# MAGI_sBatteryPowerMega-Python.net
KiCad netlist of a schematic drawn in Altium Designer
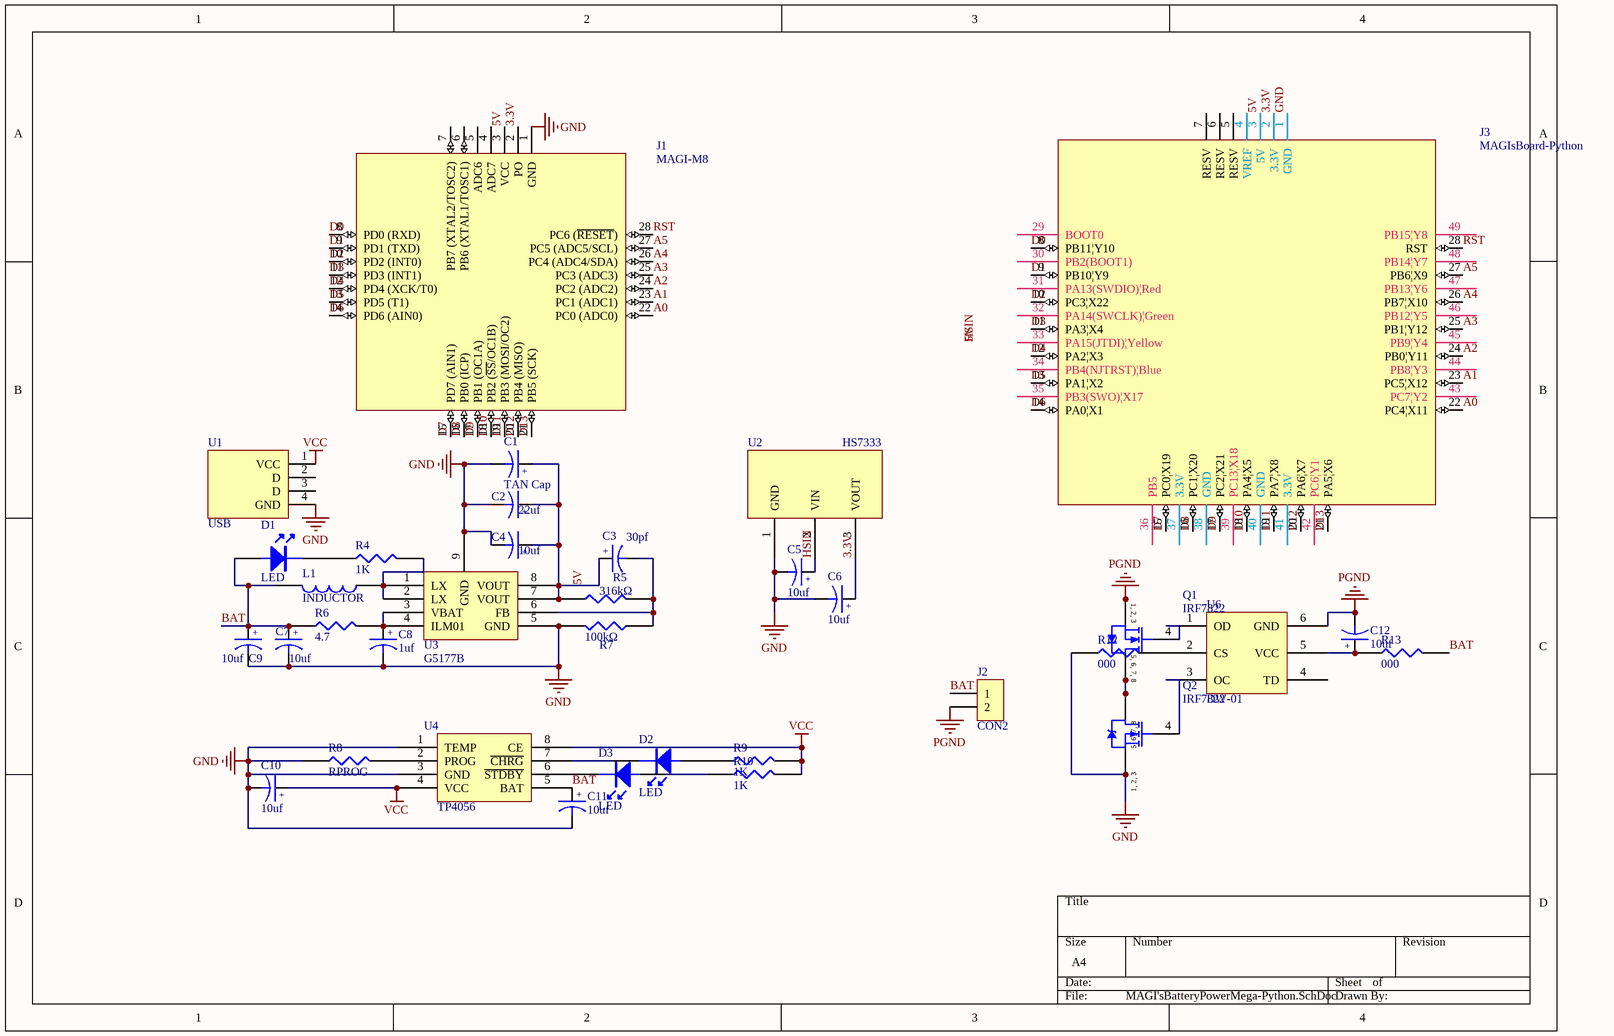
[diagram p0: MAGI'sBatteryPowerMega-Python.SchDoc]

(export (version "E")
  (design (tool "Eeschema 10.0.6"))
  (components
    (comp (ref "C1")
      (value "TAN Cap")
      (footprint "TAN-D-7343")
      (description "Capacitor")
      (libsource (lib "电容器") (part "CAPACITOR POL"))
    )
    (comp (ref "C2")
      (value "22uf")
      (footprint "14-1210")
      (description "Capacitor")
      (libsource (lib "电容器") (part "CAPACITOR POL"))
    )
    (comp (ref "C3")
      (value "30pf")
      (footprint "6-0805_N")
      (description "Capacitor")
      (libsource (lib "电容器") (part "CAPACITOR POL"))
    )
    (comp (ref "C4")
      (value "10uf")
      (footprint "6-0805_N")
      (description "Capacitor")
      (libsource (lib "电容器") (part "CAPACITOR POL"))
    )
    (comp (ref "C5")
      (value "10uf")
      (footprint "6-0805_N")
      (description "Capacitor")
      (libsource (lib "电容器") (part "CAPACITOR POL"))
    )
    (comp (ref "C6")
      (value "10uf")
      (footprint "6-0805_N")
      (description "Capacitor")
      (libsource (lib "电容器") (part "CAPACITOR POL"))
    )
    (comp (ref "C7")
      (value "10uf")
      (footprint "6-0805_N")
      (description "Capacitor")
      (libsource (lib "电容器") (part "CAPACITOR POL"))
    )
    (comp (ref "C8")
      (value "1uf")
      (footprint "6-0805_N")
      (description "Capacitor")
      (libsource (lib "电容器") (part "CAPACITOR POL"))
    )
    (comp (ref "C9")
      (value "10uf")
      (footprint "6-0805_N")
      (description "Capacitor")
      (libsource (lib "电容器") (part "CAPACITOR POL"))
    )
    (comp (ref "C10")
      (value "10uf")
      (footprint "6-0805_N")
      (description "Capacitor")
      (libsource (lib "电容器") (part "CAPACITOR POL"))
    )
    (comp (ref "C11")
      (value "10uf")
      (footprint "6-0805_N")
      (description "Capacitor")
      (libsource (lib "电容器") (part "CAPACITOR POL"))
    )
    (comp (ref "C12")
      (value "10uf")
      (footprint "6-0805_N")
      (description "Capacitor")
      (libsource (lib "电容器") (part "CAPACITOR POL"))
    )
    (comp (ref "D1") (value "LED") (footprint "6-0805_N") (libsource (lib "二极管") (part "LED")))
    (comp (ref "D2") (value "LED") (footprint "6-0805_N") (libsource (lib "二极管") (part "LED")))
    (comp (ref "D3") (value "LED") (footprint "6-0805_N") (libsource (lib "二极管") (part "LED")))
    (comp (ref "J1") (value "MAGI-M8") (footprint "MAGI-M8") (libsource (lib "MAGI-M8") (part "MAGI-M8")))
    (comp (ref "J2")
      (value "CON2")
      (footprint "18650")
      (description "Connector")
      (libsource (lib "CON系列") (part "CON2"))
    )
    (comp (ref "J3")
      (value "MAGIsBoard-Python")
      (footprint "MAGIsBoard-Python")
      (libsource (lib "MAGIsBoard") (part "MAGIsBoard-Python"))
    )
    (comp (ref "L1") (value "INDUCTOR") (footprint "7*7") (libsource (lib "汇总") (part "INDUCTOR")))
    (comp (ref "Q1")
      (value "IRF7822")
      (footprint "SO-8_N")
      (description "HEXFET Power MOSFET")
      (fields (field (name "PUBLISHER") "Altium Limited"))
      (libsource (lib "IR Discrete MOSFET - Power") (part "IRF7822"))
    )
    (comp (ref "Q2")
      (value "IRF7822")
      (footprint "SO-8_N")
      (description "HEXFET Power MOSFET")
      (fields (field (name "PUBLISHER") "Altium Limited"))
      (libsource (lib "IR Discrete MOSFET - Power") (part "IRF7822"))
    )
    (comp (ref "R4") (value "1K") (footprint "6-0805_N") (libsource (lib "电阻器") (part "RES1")))
    (comp (ref "R5") (value "316kΩ") (footprint "6-0805_N") (libsource (lib "电阻器") (part "RES1")))
    (comp (ref "R6") (value "4.7") (footprint "6-0805_N") (libsource (lib "电阻器") (part "RES1")))
    (comp (ref "R7") (value "100kΩ") (footprint "6-0805_N") (libsource (lib "电阻器") (part "RES1")))
    (comp (ref "R8") (value "RPROG") (footprint "6-0805_N") (libsource (lib "电阻器") (part "RES1")))
    (comp (ref "R9") (value "1K") (footprint "6-0805_N") (libsource (lib "电阻器") (part "RES1")))
    (comp (ref "R10") (value "1K") (footprint "6-0805_N") (libsource (lib "电阻器") (part "RES1")))
    (comp (ref "R12") (value "000") (footprint "6-0805_n") (libsource (lib "电阻器") (part "RES1")))
    (comp (ref "R13") (value "000") (footprint "6-0805_n") (libsource (lib "电阻器") (part "RES1")))
    (comp (ref "U1") (value "USB") (footprint "MicroUSB") (libsource (lib "USB接口") (part "USB")))
    (comp (ref "U2") (value "HS7333") (footprint "HS7333") (libsource (lib "PMIC") (part "HS7333")))
    (comp (ref "U3") (value "G5177B") (footprint "G5177B") (libsource (lib "PMIC") (part "G5177B")))
    (comp (ref "U4") (value "TP4056") (footprint "TP4056") (libsource (lib "PMIC") (part "TP4056")))
    (comp (ref "U6") (value "DW-01") (footprint "TPS2513") (libsource (lib "PMIC") (part "TPS2513")))
  )
  (nets
    (net (code "1") (name "/3.3V") (class "Default")
      (node (ref "C6") (pin "1") (pinfunction "1_1") (pintype "passive"))
      (node (ref "J1") (pin "2") (pinfunction "PO_2") (pintype "power_in"))
      (node (ref "J3") (pin "2") (pinfunction "3.3V_2") (pintype "power_in"))
      (node (ref "U2") (pin "3") (pinfunction "VOUT_3") (pintype "passive"))
    )
    (net (code "2") (name "/5V") (class "Default")
      (node (ref "C1") (pin "1") (pinfunction "1_1") (pintype "passive"))
      (node (ref "C2") (pin "1") (pinfunction "1_1") (pintype "passive"))
      (node (ref "C3") (pin "1") (pinfunction "1_1") (pintype "passive"))
      (node (ref "C4") (pin "1") (pinfunction "1_1") (pintype "passive"))
      (node (ref "C5") (pin "1") (pinfunction "1_1") (pintype "passive"))
      (node (ref "J1") (pin "3") (pinfunction "VCC_3") (pintype "power_in"))
      (node (ref "J3") (pin "3") (pinfunction "5V_3") (pintype "power_in"))
      (node (ref "R5") (pin "1") (pinfunction "1_1") (pintype "passive"))
      (node (ref "U2") (pin "2") (pinfunction "VIN_2") (pintype "passive"))
      (node (ref "U3") (pin "7") (pinfunction "VOUT_7") (pintype "passive"))
      (node (ref "U3") (pin "8") (pinfunction "VOUT_8") (pintype "passive"))
    )
    (net (code "3") (name "/A0") (class "Default")
      (node (ref "J1") (pin "22") (pinfunction "PC0_(ADC0)_22") (pintype "bidirectional"))
      (node (ref "J3") (pin "22") (pinfunction "PC4¦X11_22") (pintype "bidirectional"))
    )
    (net (code "4") (name "/A1") (class "Default")
      (node (ref "J1") (pin "23") (pinfunction "PC1_(ADC1)_23") (pintype "bidirectional"))
      (node (ref "J3") (pin "23") (pinfunction "PC5¦X12_23") (pintype "bidirectional"))
    )
    (net (code "5") (name "/A2") (class "Default")
      (node (ref "J1") (pin "24") (pinfunction "PC2_(ADC2)_24") (pintype "bidirectional"))
      (node (ref "J3") (pin "24") (pinfunction "PB0¦Y11_24") (pintype "bidirectional"))
    )
    (net (code "6") (name "/A3") (class "Default")
      (node (ref "J1") (pin "25") (pinfunction "PC3_(ADC3)_25") (pintype "bidirectional"))
      (node (ref "J3") (pin "25") (pinfunction "PB1¦Y12_25") (pintype "bidirectional"))
    )
    (net (code "7") (name "/A4") (class "Default")
      (node (ref "J1") (pin "26") (pinfunction "PC4_(ADC4/SDA)_26") (pintype "bidirectional"))
      (node (ref "J3") (pin "26") (pinfunction "PB7¦X10_26") (pintype "bidirectional"))
    )
    (net (code "8") (name "/A5") (class "Default")
      (node (ref "J1") (pin "27") (pinfunction "PC5_(ADC5/SCL)_27") (pintype "bidirectional"))
      (node (ref "J3") (pin "27") (pinfunction "PB6¦X9_27") (pintype "bidirectional"))
    )
    (net (code "9") (name "/BAT") (class "Default")
      (node (ref "C11") (pin "1") (pinfunction "1_1") (pintype "passive"))
      (node (ref "C7") (pin "1") (pinfunction "1_1") (pintype "passive"))
      (node (ref "C9") (pin "1") (pinfunction "1_1") (pintype "passive"))
      (node (ref "D1") (pin "1") (pinfunction "1_1") (pintype "passive"))
      (node (ref "J2") (pin "1") (pinfunction "1_1") (pintype "passive"))
      (node (ref "L1") (pin "2") (pinfunction "2_2") (pintype "passive"))
      (node (ref "R13") (pin "2") (pinfunction "2_2") (pintype "passive"))
      (node (ref "R6") (pin "1") (pinfunction "1_1") (pintype "passive"))
      (node (ref "U4") (pin "5") (pinfunction "BAT_5") (pintype "passive"))
    )
    (net (code "10") (name "/D0") (class "Default")
      (node (ref "J1") (pin "8") (pinfunction "PD0_(RXD)_8") (pintype "bidirectional"))
      (node (ref "J3") (pin "8") (pinfunction "PB11¦Y10_8") (pintype "bidirectional"))
    )
    (net (code "11") (name "/D1") (class "Default")
      (node (ref "J1") (pin "9") (pinfunction "PD1_(TXD)_9") (pintype "bidirectional"))
      (node (ref "J3") (pin "9") (pinfunction "PB10¦Y9_9") (pintype "bidirectional"))
    )
    (net (code "12") (name "/D2") (class "Default")
      (node (ref "J1") (pin "10") (pinfunction "PD2_(INT0)_10") (pintype "bidirectional"))
      (node (ref "J3") (pin "10") (pinfunction "PC3¦X22_10") (pintype "bidirectional"))
    )
    (net (code "13") (name "/D3") (class "Default")
      (node (ref "J1") (pin "11") (pinfunction "PD3_(INT1)_11") (pintype "bidirectional"))
      (node (ref "J3") (pin "11") (pinfunction "PA3¦X4_11") (pintype "bidirectional"))
    )
    (net (code "14") (name "/D4") (class "Default")
      (node (ref "J1") (pin "12") (pinfunction "PD4_(XCK/T0)_12") (pintype "bidirectional"))
      (node (ref "J3") (pin "12") (pinfunction "PA2¦X3_12") (pintype "bidirectional"))
    )
    (net (code "15") (name "/D5") (class "Default")
      (node (ref "J1") (pin "13") (pinfunction "PD5_(T1)_13") (pintype "bidirectional"))
      (node (ref "J3") (pin "13") (pinfunction "PA1¦X2_13") (pintype "bidirectional"))
    )
    (net (code "16") (name "/D6") (class "Default")
      (node (ref "J1") (pin "14") (pinfunction "PD6_(AIN0)_14") (pintype "bidirectional"))
      (node (ref "J3") (pin "14") (pinfunction "PA0¦X1_14") (pintype "bidirectional"))
    )
    (net (code "17") (name "/D7") (class "Default")
      (node (ref "J1") (pin "15") (pinfunction "PD7_(AIN1)_15") (pintype "bidirectional"))
      (node (ref "J3") (pin "15") (pinfunction "PC0¦X19_15") (pintype "bidirectional"))
    )
    (net (code "18") (name "/D8") (class "Default")
      (node (ref "J1") (pin "16") (pinfunction "PB0_(ICP)_16") (pintype "bidirectional"))
      (node (ref "J3") (pin "16") (pinfunction "PC1¦X20_16") (pintype "bidirectional"))
    )
    (net (code "19") (name "/D9") (class "Default")
      (node (ref "J1") (pin "17") (pinfunction "PB1_(OC1A)_17") (pintype "bidirectional"))
      (node (ref "J3") (pin "17") (pinfunction "PC2¦X21_17") (pintype "bidirectional"))
    )
    (net (code "20") (name "/D10") (class "Default")
      (node (ref "J1") (pin "18") (pinfunction "PB2_(~{SS}/OC1B)_18") (pintype "bidirectional"))
      (node (ref "J3") (pin "18") (pinfunction "PA4¦X5_18") (pintype "bidirectional"))
    )
    (net (code "21") (name "/D11") (class "Default")
      (node (ref "J1") (pin "19") (pinfunction "PB3_(MOSI/OC2)_19") (pintype "bidirectional"))
      (node (ref "J3") (pin "19") (pinfunction "PA7¦X8_19") (pintype "bidirectional"))
    )
    (net (code "22") (name "/D12") (class "Default")
      (node (ref "J1") (pin "20") (pinfunction "PB4_(MISO)_20") (pintype "bidirectional"))
      (node (ref "J3") (pin "20") (pinfunction "PA6¦X7_20") (pintype "bidirectional"))
    )
    (net (code "23") (name "/D13") (class "Default")
      (node (ref "J1") (pin "21") (pinfunction "PB5_(SCK)_21") (pintype "bidirectional"))
      (node (ref "J3") (pin "21") (pinfunction "PA5¦X6_21") (pintype "bidirectional"))
    )
    (net (code "24") (name "/RST") (class "Default")
      (node (ref "J1") (pin "28") (pinfunction "PC6_(~{RESET})_28") (pintype "bidirectional"))
      (node (ref "J3") (pin "28") (pinfunction "RST_28") (pintype "bidirectional"))
    )
    (net (code "25") (name "GND") (class "Default")
      (node (ref "C1") (pin "2") (pinfunction "2_2") (pintype "passive"))
      (node (ref "C10") (pin "2") (pinfunction "2_2") (pintype "passive"))
      (node (ref "C11") (pin "2") (pinfunction "2_2") (pintype "passive"))
      (node (ref "C2") (pin "2") (pinfunction "2_2") (pintype "passive"))
      (node (ref "C4") (pin "2") (pinfunction "2_2") (pintype "passive"))
      (node (ref "C5") (pin "2") (pinfunction "2_2") (pintype "passive"))
      (node (ref "C6") (pin "2") (pinfunction "2_2") (pintype "passive"))
      (node (ref "C7") (pin "2") (pinfunction "2_2") (pintype "passive"))
      (node (ref "C8") (pin "2") (pinfunction "2_2") (pintype "passive"))
      (node (ref "C9") (pin "2") (pinfunction "2_2") (pintype "passive"))
      (node (ref "J1") (pin "1") (pinfunction "GND_1") (pintype "power_in"))
      (node (ref "J3") (pin "1") (pinfunction "GND_1") (pintype "power_in"))
      (node (ref "Q2") (pin "1") (pinfunction "S_1") (pintype "passive"))
      (node (ref "Q2") (pin "2") (pinfunction "S_2") (pintype "passive"))
      (node (ref "Q2") (pin "3") (pinfunction "S_3") (pintype "passive"))
      (node (ref "R12") (pin "1") (pinfunction "1_1") (pintype "passive"))
      (node (ref "R7") (pin "2") (pinfunction "2_2") (pintype "passive"))
      (node (ref "R8") (pin "1") (pinfunction "1_1") (pintype "passive"))
      (node (ref "U1") (pin "4") (pinfunction "GND_4") (pintype "passive"))
      (node (ref "U2") (pin "1") (pinfunction "GND_1") (pintype "passive"))
      (node (ref "U3") (pin "5") (pinfunction "GND_5") (pintype "passive"))
      (node (ref "U3") (pin "9") (pinfunction "GND_9") (pintype "passive"))
      (node (ref "U4") (pin "1") (pinfunction "TEMP_1") (pintype "passive"))
      (node (ref "U4") (pin "3") (pinfunction "GND_3") (pintype "passive"))
    )
    (net (code "26") (name "Net-(D1-Pad2)") (class "Default")
      (node (ref "D1") (pin "2") (pinfunction "2_2") (pintype "passive"))
      (node (ref "R4") (pin "1") (pinfunction "1_1") (pintype "passive"))
    )
    (net (code "27") (name "Net-(D2-Pad1)") (class "Default")
      (node (ref "D2") (pin "1") (pinfunction "1_1") (pintype "passive"))
      (node (ref "R9") (pin "1") (pinfunction "1_1") (pintype "passive"))
    )
    (net (code "28") (name "Net-(D3-Pad1)") (class "Default")
      (node (ref "D3") (pin "1") (pinfunction "1_1") (pintype "passive"))
      (node (ref "R10") (pin "1") (pinfunction "1_1") (pintype "passive"))
    )
    (net (code "29") (name "Net-(L1-Pad1)") (class "Default")
      (node (ref "L1") (pin "1") (pinfunction "1_1") (pintype "passive"))
      (node (ref "R4") (pin "2") (pinfunction "2_2") (pintype "passive"))
      (node (ref "U3") (pin "1") (pinfunction "LX_1") (pintype "passive"))
      (node (ref "U3") (pin "2") (pinfunction "LX_2") (pintype "passive"))
    )
    (net (code "30") (name "Net-(Q1-D-Pad5)") (class "Default")
      (node (ref "Q1") (pin "5") (pinfunction "D_5") (pintype "passive"))
      (node (ref "Q1") (pin "6") (pinfunction "D_6") (pintype "passive"))
      (node (ref "Q1") (pin "7") (pinfunction "D_7") (pintype "passive"))
      (node (ref "Q1") (pin "8") (pinfunction "D_8") (pintype "passive"))
      (node (ref "Q2") (pin "5") (pinfunction "D_5") (pintype "passive"))
      (node (ref "Q2") (pin "6") (pinfunction "D_6") (pintype "passive"))
      (node (ref "Q2") (pin "7") (pinfunction "D_7") (pintype "passive"))
      (node (ref "Q2") (pin "8") (pinfunction "D_8") (pintype "passive"))
    )
    (net (code "31") (name "Net-(Q1-G)") (class "Default")
      (node (ref "Q1") (pin "4") (pinfunction "G_4") (pintype "passive"))
      (node (ref "U6") (pin "1") (pinfunction "OD_1") (pintype "passive"))
    )
    (net (code "32") (name "Net-(Q2-G)") (class "Default")
      (node (ref "Q2") (pin "4") (pinfunction "G_4") (pintype "passive"))
      (node (ref "U6") (pin "3") (pinfunction "OC_3") (pintype "passive"))
    )
    (net (code "33") (name "Net-(U3-FB)") (class "Default")
      (node (ref "C3") (pin "2") (pinfunction "2_2") (pintype "passive"))
      (node (ref "R5") (pin "2") (pinfunction "2_2") (pintype "passive"))
      (node (ref "R7") (pin "1") (pinfunction "1_1") (pintype "passive"))
      (node (ref "U3") (pin "6") (pinfunction "FB_6") (pintype "passive"))
    )
    (net (code "34") (name "Net-(U3-ILM01)") (class "Default")
      (node (ref "C8") (pin "1") (pinfunction "1_1") (pintype "passive"))
      (node (ref "R6") (pin "2") (pinfunction "2_2") (pintype "passive"))
      (node (ref "U3") (pin "3") (pinfunction "VBAT_3") (pintype "passive"))
      (node (ref "U3") (pin "4") (pinfunction "ILM01_4") (pintype "passive"))
    )
    (net (code "35") (name "Net-(U4-PROG)") (class "Default")
      (node (ref "R8") (pin "2") (pinfunction "2_2") (pintype "passive"))
      (node (ref "U4") (pin "2") (pinfunction "PROG_2") (pintype "passive"))
    )
    (net (code "36") (name "Net-(U4-~{CHRG})") (class "Default")
      (node (ref "D2") (pin "2") (pinfunction "2_2") (pintype "passive"))
      (node (ref "U4") (pin "7") (pinfunction "~{CHRG}_7") (pintype "passive"))
    )
    (net (code "37") (name "Net-(U4-~{STDBY})") (class "Default")
      (node (ref "D3") (pin "2") (pinfunction "2_2") (pintype "passive"))
      (node (ref "U4") (pin "6") (pinfunction "~{STDBY}_6") (pintype "passive"))
    )
    (net (code "38") (name "Net-(U6-CS)") (class "Default")
      (node (ref "R12") (pin "2") (pinfunction "2_2") (pintype "passive"))
      (node (ref "U6") (pin "2") (pinfunction "CS_2") (pintype "passive"))
    )
    (net (code "39") (name "Net-(U6-VCC)") (class "Default")
      (node (ref "C12") (pin "1") (pinfunction "1_1") (pintype "passive"))
      (node (ref "R13") (pin "1") (pinfunction "1_1") (pintype "passive"))
      (node (ref "U6") (pin "5") (pinfunction "VCC_5") (pintype "passive"))
    )
    (net (code "40") (name "PGND") (class "Default")
      (node (ref "C12") (pin "2") (pinfunction "2_2") (pintype "passive"))
      (node (ref "J2") (pin "2") (pinfunction "2_2") (pintype "passive"))
      (node (ref "Q1") (pin "1") (pinfunction "S_1") (pintype "passive"))
      (node (ref "Q1") (pin "2") (pinfunction "S_2") (pintype "passive"))
      (node (ref "Q1") (pin "3") (pinfunction "S_3") (pintype "passive"))
      (node (ref "U6") (pin "6") (pinfunction "GND_6") (pintype "passive"))
    )
    (net (code "41") (name "VCC") (class "Default")
      (node (ref "C10") (pin "1") (pinfunction "1_1") (pintype "passive"))
      (node (ref "R10") (pin "2") (pinfunction "2_2") (pintype "passive"))
      (node (ref "R9") (pin "2") (pinfunction "2_2") (pintype "passive"))
      (node (ref "U1") (pin "1") (pinfunction "VCC_1") (pintype "passive"))
      (node (ref "U4") (pin "4") (pinfunction "VCC_4") (pintype "passive"))
      (node (ref "U4") (pin "8") (pinfunction "CE_8") (pintype "passive"))
    )
    (net (code "42") (name "unconnected-(J1-ADC6-Pad5)") (class "Default")
      (node (ref "J1") (pin "5") (pinfunction "ADC6_5") (pintype "passive"))
    )
    (net (code "43") (name "unconnected-(J1-ADC7-Pad4)") (class "Default")
      (node (ref "J1") (pin "4") (pinfunction "ADC7_4") (pintype "passive"))
    )
    (net (code "44") (name "unconnected-(J1-PB6_(XTAL1{slash}TOSC1)-Pad6)") (class "Default")
      (node (ref "J1") (pin "6") (pinfunction "PB6_(XTAL1/TOSC1)_6") (pintype "bidirectional"))
    )
    (net (code "45") (name "unconnected-(J1-PB7_(XTAL2{slash}TOSC2)-Pad7)") (class "Default")
      (node (ref "J1") (pin "7") (pinfunction "PB7_(XTAL2/TOSC2)_7") (pintype "bidirectional"))
    )
    (net (code "46") (name "unconnected-(J3-3.3V-Pad37)") (class "Default")
      (node (ref "J3") (pin "37") (pinfunction "3.3V_37") (pintype "passive"))
    )
    (net (code "47") (name "unconnected-(J3-3.3V-Pad41)") (class "Default")
      (node (ref "J3") (pin "41") (pinfunction "3.3V_41") (pintype "passive"))
    )
    (net (code "48") (name "unconnected-(J3-BOOT0-Pad29)") (class "Default")
      (node (ref "J3") (pin "29") (pinfunction "BOOT0_29") (pintype "passive"))
    )
    (net (code "49") (name "unconnected-(J3-GND-Pad38)") (class "Default")
      (node (ref "J3") (pin "38") (pinfunction "GND_38") (pintype "passive"))
    )
    (net (code "50") (name "unconnected-(J3-GND-Pad40)") (class "Default")
      (node (ref "J3") (pin "40") (pinfunction "GND_40") (pintype "passive"))
    )
    (net (code "51") (name "unconnected-(J3-PA13(SWDIO)¦Red-Pad31)") (class "Default")
      (node (ref "J3") (pin "31") (pinfunction "PA13(SWDIO)¦Red_31") (pintype "passive"))
    )
    (net (code "52") (name "unconnected-(J3-PA14(SWCLK)¦Green-Pad32)") (class "Default")
      (node (ref "J3") (pin "32") (pinfunction "PA14(SWCLK)¦Green_32") (pintype "passive"))
    )
    (net (code "53") (name "unconnected-(J3-PA15(JTDI)¦Yellow-Pad33)") (class "Default")
      (node (ref "J3") (pin "33") (pinfunction "PA15(JTDI)¦Yellow_33") (pintype "passive"))
    )
    (net (code "54") (name "unconnected-(J3-PB2(BOOT1)-Pad30)") (class "Default")
      (node (ref "J3") (pin "30") (pinfunction "PB2(BOOT1)_30") (pintype "passive"))
    )
    (net (code "55") (name "unconnected-(J3-PB3(SWO)¦X17-Pad35)") (class "Default")
      (node (ref "J3") (pin "35") (pinfunction "PB3(SWO)¦X17_35") (pintype "passive"))
    )
    (net (code "56") (name "unconnected-(J3-PB4(NJTRST)¦Blue-Pad34)") (class "Default")
      (node (ref "J3") (pin "34") (pinfunction "PB4(NJTRST)¦Blue_34") (pintype "passive"))
    )
    (net (code "57") (name "unconnected-(J3-PB5-Pad36)") (class "Default")
      (node (ref "J3") (pin "36") (pinfunction "PB5_36") (pintype "passive"))
    )
    (net (code "58") (name "unconnected-(J3-PB8¦Y3-Pad44)") (class "Default")
      (node (ref "J3") (pin "44") (pinfunction "PB8¦Y3_44") (pintype "passive"))
    )
    (net (code "59") (name "unconnected-(J3-PB9¦Y4-Pad45)") (class "Default")
      (node (ref "J3") (pin "45") (pinfunction "PB9¦Y4_45") (pintype "passive"))
    )
    (net (code "60") (name "unconnected-(J3-PB12¦Y5-Pad46)") (class "Default")
      (node (ref "J3") (pin "46") (pinfunction "PB12¦Y5_46") (pintype "passive"))
    )
    (net (code "61") (name "unconnected-(J3-PB13¦Y6-Pad47)") (class "Default")
      (node (ref "J3") (pin "47") (pinfunction "PB13¦Y6_47") (pintype "passive"))
    )
    (net (code "62") (name "unconnected-(J3-PB14¦Y7-Pad48)") (class "Default")
      (node (ref "J3") (pin "48") (pinfunction "PB14¦Y7_48") (pintype "passive"))
    )
    (net (code "63") (name "unconnected-(J3-PB15¦Y8-Pad49)") (class "Default")
      (node (ref "J3") (pin "49") (pinfunction "PB15¦Y8_49") (pintype "passive"))
    )
    (net (code "64") (name "unconnected-(J3-PC6¦Y1-Pad42)") (class "Default")
      (node (ref "J3") (pin "42") (pinfunction "PC6¦Y1_42") (pintype "passive"))
    )
    (net (code "65") (name "unconnected-(J3-PC7¦Y2-Pad43)") (class "Default")
      (node (ref "J3") (pin "43") (pinfunction "PC7¦Y2_43") (pintype "passive"))
    )
    (net (code "66") (name "unconnected-(J3-PC13¦X18-Pad39)") (class "Default")
      (node (ref "J3") (pin "39") (pinfunction "PC13¦X18_39") (pintype "passive"))
    )
    (net (code "67") (name "unconnected-(J3-RESV-Pad5)") (class "Default")
      (node (ref "J3") (pin "5") (pinfunction "RESV_5") (pintype "passive"))
    )
    (net (code "68") (name "unconnected-(J3-RESV-Pad6)") (class "Default")
      (node (ref "J3") (pin "6") (pinfunction "RESV_6") (pintype "passive"))
    )
    (net (code "69") (name "unconnected-(J3-RESV-Pad7)") (class "Default")
      (node (ref "J3") (pin "7") (pinfunction "RESV_7") (pintype "passive"))
    )
    (net (code "70") (name "unconnected-(J3-VREF-Pad4)") (class "Default")
      (node (ref "J3") (pin "4") (pinfunction "VREF_4") (pintype "passive"))
    )
    (net (code "71") (name "unconnected-(U1-D-Pad2)") (class "Default")
      (node (ref "U1") (pin "2") (pinfunction "D_2") (pintype "passive"))
    )
    (net (code "72") (name "unconnected-(U1-D-Pad3)") (class "Default")
      (node (ref "U1") (pin "3") (pinfunction "D_3") (pintype "passive"))
    )
    (net (code "73") (name "unconnected-(U6-TD-Pad4)") (class "Default")
      (node (ref "U6") (pin "4") (pinfunction "TD_4") (pintype "passive"))
    )
  )
)
